# boombox_power_high_amp.net
KiCad netlist of a schematic drawn in EAGLE
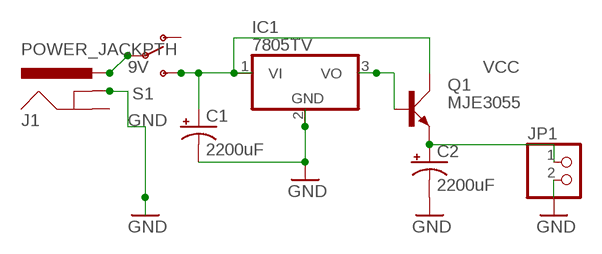
[diagram p0: schematic, sheet 1]

(export (version "E")
  (design (tool "Eeschema 10.0.6"))
  (components
    (comp (ref "C1")
      (value "2200uF")
      (footprint "eagle-import:CPOL-RADIAL-1000UF-25V")
      (libsource (lib "eagle-import") (part "CAP_POLPTH4"))
    )
    (comp (ref "C2")
      (value "2200uF")
      (footprint "eagle-import:CPOL-RADIAL-1000UF-25V")
      (libsource (lib "eagle-import") (part "CAP_POLPTH4"))
    )
    (comp (ref "IC1")
      (value "7805TV")
      (footprint "eagle-import:TO220V")
      (libsource (lib "eagle-import") (part "78TV05"))
    )
    (comp (ref "J1")
      (value "POWER_JACKPTH")
      (footprint "eagle-import:POWER_JACK_PTH")
      (libsource (lib "eagle-import") (part "POWER_JACKPTH"))
    )
    (comp (ref "JP1")
      (value "PINHD-1X2")
      (footprint "eagle-import:1X02")
      (libsource (lib "eagle-import") (part "PINHD-1X2"))
    )
    (comp (ref "Q1")
      (value "MJE3055")
      (footprint "eagle-import:TO220AV")
      (libsource (lib "eagle-import") (part "MJE3055"))
    )
    (comp (ref "S1")
      (value "SWITCH-SPSTPTH")
      (footprint "eagle-import:SWITCH-SPDT")
      (libsource (lib "eagle-import") (part "SWITCH-SPSTPTH"))
    )
  )
  (nets
    (net (code "1") (name "/9V") (class "Default")
      (node (ref "C1") (pin "1") (pinfunction "+_1") (pintype "passive"))
      (node (ref "IC1") (pin "1") (pinfunction "VI_1") (pintype "input"))
      (node (ref "Q1") (pin "C") (pinfunction "C_C") (pintype "passive"))
      (node (ref "S1") (pin "3") (pinfunction "S_3") (pintype "passive"))
    )
    (net (code "2") (name "/VCC") (class "Default")
      (node (ref "IC1") (pin "3") (pinfunction "VO_3") (pintype "passive"))
      (node (ref "Q1") (pin "B") (pinfunction "B_B") (pintype "passive"))
    )
    (net (code "3") (name "GND") (class "Default")
      (node (ref "C1") (pin "2") (pinfunction "-_2") (pintype "passive"))
      (node (ref "C2") (pin "2") (pinfunction "-_2") (pintype "passive"))
      (node (ref "IC1") (pin "2") (pinfunction "GND_2") (pintype "passive"))
      (node (ref "J1") (pin "GNDBREAK") (pinfunction "GNDBREAK_GNDBREAK") (pintype "bidirectional"))
      (node (ref "JP1") (pin "2") (pinfunction "2_2") (pintype "passive"))
    )
    (net (code "4") (name "Net-(C2-+)") (class "Default")
      (node (ref "C2") (pin "1") (pinfunction "+_1") (pintype "passive"))
      (node (ref "JP1") (pin "1") (pinfunction "1_1") (pintype "passive"))
      (node (ref "Q1") (pin "E") (pinfunction "E_E") (pintype "passive"))
    )
    (net (code "5") (name "Net-(S1-P)") (class "Default")
      (node (ref "J1") (pin "PWR") (pinfunction "PWR_PWR") (pintype "bidirectional"))
      (node (ref "S1") (pin "2") (pinfunction "P_2") (pintype "passive"))
    )
    (net (code "6") (name "unconnected-(J1-PadGND)") (class "Default")
      (node (ref "J1") (pin "GND") (pinfunction "GND_GND") (pintype "bidirectional"))
    )
    (net (code "7") (name "unconnected-(S1-O-Pad1)") (class "Default")
      (node (ref "S1") (pin "1") (pinfunction "O_1") (pintype "passive"))
    )
  )
)
